# ERT-_Exciting_Source.net
KiCad netlist of a schematic drawn in Altium Designer
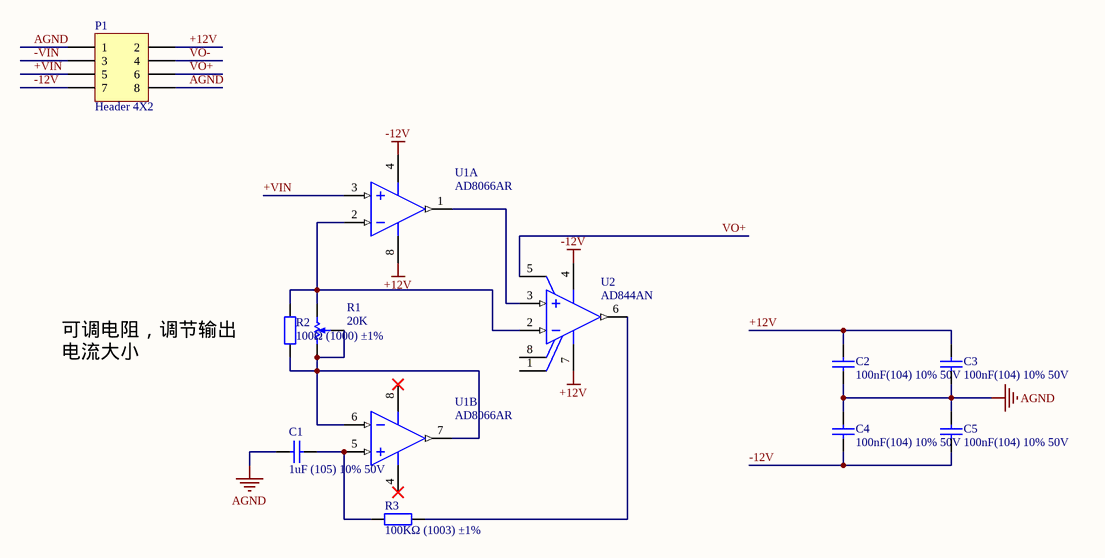
[diagram p0: ERT- Exciting Source.SchDoc]

(export (version "E")
  (design (tool "Eeschema 10.0.6"))
  (components
    (comp (ref "C1")
      (value "1uF (105) 10% 50V")
      (footprint "LC-0805_C")
      (description "贴片电容")
      (libsource (lib "Miscellaneous Devices LC") (part "0805 1uF (105) 10% 50V"))
    )
    (comp (ref "C2")
      (value "100nF(104) 10% 50V")
      (footprint "LC-0805_C")
      (description "贴片电容")
      (libsource (lib "Miscellaneous Devices LC") (part "0805 100nF(104) 10% 50V"))
    )
    (comp (ref "C3")
      (value "100nF(104) 10% 50V")
      (footprint "LC-0805_C")
      (description "贴片电容")
      (libsource (lib "Miscellaneous Devices LC") (part "0805 100nF(104) 10% 50V"))
    )
    (comp (ref "C4")
      (value "100nF(104) 10% 50V")
      (footprint "LC-0805_C")
      (description "贴片电容")
      (libsource (lib "Miscellaneous Devices LC") (part "0805 100nF(104) 10% 50V"))
    )
    (comp (ref "C5")
      (value "100nF(104) 10% 50V")
      (footprint "LC-0805_C")
      (description "贴片电容")
      (libsource (lib "Miscellaneous Devices LC") (part "0805 100nF(104) 10% 50V"))
    )
    (comp (ref "P1")
      (value "Header 4X2")
      (footprint "HDR2X4")
      (description "Header, 4-Pin, Dual row")
      (fields (field (name "PUBLISHER") "Altium Limited"))
      (libsource (lib "Miscellaneous Connectors") (part "Header 4X2"))
    )
    (comp (ref "R1")
      (value "20K")
      (footprint "POT4MM-2")
      (description "Square Trimming Potentiometer")
      (fields (field (name "PUBLISHER") "Altium Limited"))
      (libsource (lib "Miscellaneous Devices") (part "RPot SM"))
    )
    (comp (ref "R2")
      (value "100Ω (1000) ±1%")
      (footprint "LC-0805_R")
      (description "贴片电阻")
      (libsource (lib "Miscellaneous Devices LC") (part "0805 100Ω (1000) 1%"))
    )
    (comp (ref "R3")
      (value "100KΩ (1003) ±1%")
      (footprint "LC-0805_R")
      (description "贴片电阻")
      (libsource (lib "Miscellaneous Devices LC") (part "0805 100KΩ (1003) 1%"))
    )
    (comp (ref "U1")
      (value "AD8066AR")
      (footprint "ADI-R-8_N")
      (fields (field (name "GENERIC PART NUMBER") "AD8066") (field (name "MANUFACTURER") "Analog Devices"))
      (libsource (lib "Analog Devices Operational Amplifiers") (part "AD8066AR"))
    )
    (comp (ref "U2")
      (value "AD844AN")
      (footprint "ADI-N-8")
      (fields (field (name "GENERIC PART NUMBER") "AD844") (field (name "MANUFACTURER") "Analog Devices"))
      (libsource (lib "Analog Devices Operational Amplifiers") (part "AD844AN"))
    )
  )
  (nets
    (net (code "1") (name "+12V") (class "Default")
      (node (ref "C2") (pin "2") (pinfunction "2_2") (pintype "passive"))
      (node (ref "C3") (pin "2") (pinfunction "2_2") (pintype "passive"))
      (node (ref "P1") (pin "2") (pinfunction "2_2") (pintype "passive"))
      (node (ref "U1") (pin "8") (pinfunction "+VS_8") (pintype "power_in"))
      (node (ref "U2") (pin "7") (pinfunction "+VS_7") (pintype "power_in"))
    )
    (net (code "2") (name "-12V") (class "Default")
      (node (ref "C4") (pin "1") (pinfunction "1_1") (pintype "passive"))
      (node (ref "C5") (pin "1") (pinfunction "1_1") (pintype "passive"))
      (node (ref "P1") (pin "7") (pinfunction "7_7") (pintype "passive"))
      (node (ref "U1") (pin "4") (pinfunction "-VS_4") (pintype "power_in"))
      (node (ref "U2") (pin "4") (pinfunction "-VS_4") (pintype "power_in"))
    )
    (net (code "3") (name "/+VIN") (class "Default")
      (node (ref "P1") (pin "5") (pinfunction "5_5") (pintype "passive"))
      (node (ref "U1") (pin "3") (pinfunction "+IN_1_3") (pintype "input"))
    )
    (net (code "4") (name "/-VIN") (class "Default")
      (node (ref "P1") (pin "3") (pinfunction "3_3") (pintype "passive"))
    )
    (net (code "5") (name "/VO+") (class "Default")
      (node (ref "P1") (pin "6") (pinfunction "6_6") (pintype "passive"))
      (node (ref "U2") (pin "5") (pinfunction "TZ_5") (pintype "passive"))
    )
    (net (code "6") (name "/VO-") (class "Default")
      (node (ref "P1") (pin "4") (pinfunction "4_4") (pintype "passive"))
    )
    (net (code "7") (name "AGND") (class "Default")
      (node (ref "C1") (pin "1") (pinfunction "1_1") (pintype "passive"))
      (node (ref "C2") (pin "1") (pinfunction "1_1") (pintype "passive"))
      (node (ref "C3") (pin "1") (pinfunction "1_1") (pintype "passive"))
      (node (ref "C4") (pin "2") (pinfunction "2_2") (pintype "passive"))
      (node (ref "C5") (pin "2") (pinfunction "2_2") (pintype "passive"))
      (node (ref "P1") (pin "1") (pinfunction "1_1") (pintype "passive"))
      (node (ref "P1") (pin "8") (pinfunction "8_8") (pintype "passive"))
    )
    (net (code "8") (name "Net-(R1-+)") (class "Default")
      (node (ref "R1") (pin "CW") (pinfunction "+_CW") (pintype "passive"))
      (node (ref "R2") (pin "2") (pinfunction "2_2") (pintype "passive"))
      (node (ref "U1") (pin "2") (pinfunction "-IN_1_2") (pintype "input"))
      (node (ref "U2") (pin "2") (pinfunction "-IN_2") (pintype "input"))
    )
    (net (code "9") (name "Net-(R1--)") (class "Default")
      (node (ref "R1") (pin "CCW") (pinfunction "-_CCW") (pintype "passive"))
      (node (ref "R1") (pin "W") (pinfunction "W_W") (pintype "passive"))
      (node (ref "R2") (pin "1") (pinfunction "1_1") (pintype "passive"))
      (node (ref "U1") (pin "6") (pinfunction "-IN_2_6") (pintype "input"))
      (node (ref "U1") (pin "7") (pinfunction "VOUT_2_7") (pintype "output"))
    )
    (net (code "10") (name "Net-(U1A-VOUT_1)") (class "Default")
      (node (ref "U1") (pin "1") (pinfunction "VOUT_1_1") (pintype "output"))
      (node (ref "U2") (pin "3") (pinfunction "+IN_3") (pintype "input"))
    )
    (net (code "11") (name "Net-(U1B-+IN_2)") (class "Default")
      (node (ref "C1") (pin "2") (pinfunction "2_2") (pintype "passive"))
      (node (ref "R3") (pin "1") (pinfunction "1_1") (pintype "passive"))
      (node (ref "U1") (pin "5") (pinfunction "+IN_2_5") (pintype "input"))
    )
    (net (code "12") (name "Net-(U2-OUTPUT)") (class "Default")
      (node (ref "R3") (pin "2") (pinfunction "2_2") (pintype "passive"))
      (node (ref "U2") (pin "6") (pinfunction "OUTPUT_6") (pintype "output"))
    )
    (net (code "13") (name "unconnected-(U1B-+VS-Pad8)") (class "Default")
      (node (ref "U1") (pin "8") (pinfunction "+VS_8") (pintype "power_in+no_connect"))
    )
    (net (code "14") (name "unconnected-(U1B--VS-Pad4)") (class "Default")
      (node (ref "U1") (pin "4") (pinfunction "-VS_4") (pintype "power_in+no_connect"))
    )
    (net (code "15") (name "unconnected-(U2-NULL-Pad1)") (class "Default")
      (node (ref "U2") (pin "1") (pinfunction "NULL_1") (pintype "passive"))
    )
    (net (code "16") (name "unconnected-(U2-NULL-Pad8)") (class "Default")
      (node (ref "U2") (pin "8") (pinfunction "NULL_8") (pintype "passive"))
    )
  )
)
